# 1-POWER.net
KiCad netlist of a schematic drawn in Altium Designer
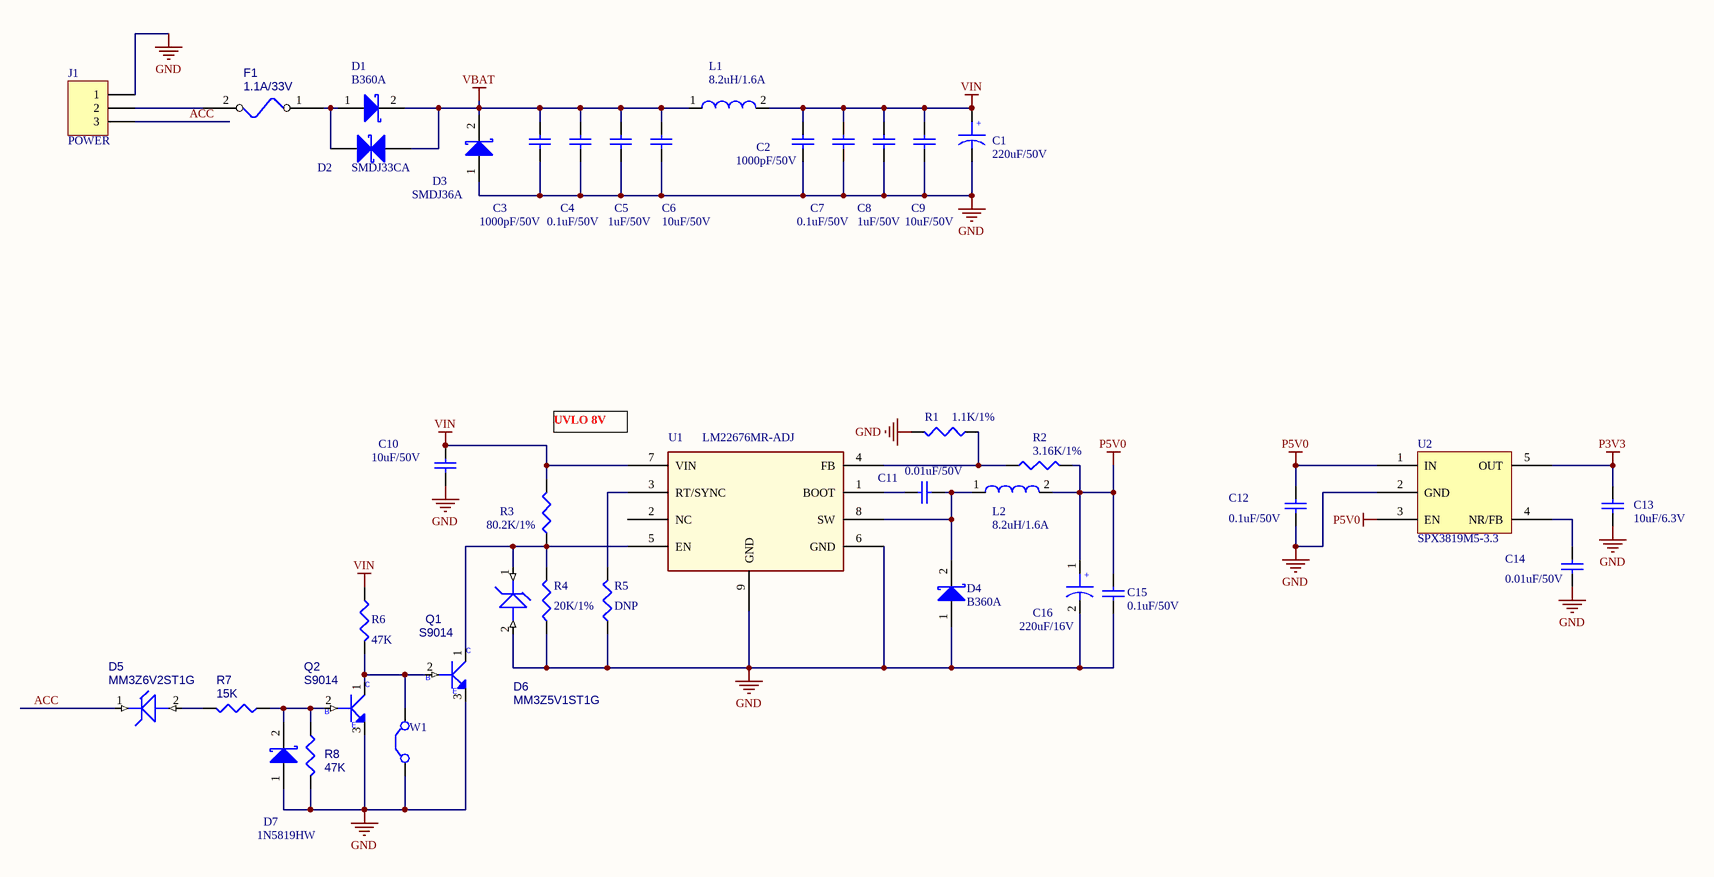
[diagram p0: 1-POWER.SchDoc]

(export (version "E")
  (design (tool "Eeschema 10.0.6"))
  (components
    (comp (ref "C1") (value "220uF/50V") (footprint "DL-10*10.5") (libsource (lib "") (part "CAP WP_1")))
    (comp (ref "C2")
      (value "1000pF/50V")
      (footprint "0402")
      (description "Capacitor")
      (fields (field (name "PUBLISHER") "Altium Limited"))
      (libsource (lib "Miscellaneous Devices") (part "Cap"))
    )
    (comp (ref "C3")
      (value "1000pF/50V")
      (footprint "0402")
      (description "Capacitor")
      (fields (field (name "PUBLISHER") "Altium Limited"))
      (libsource (lib "Miscellaneous Devices") (part "Cap"))
    )
    (comp (ref "C4")
      (value "0.1uF/50V")
      (footprint "0402")
      (description "Capacitor")
      (fields (field (name "PUBLISHER") "Altium Limited"))
      (libsource (lib "Miscellaneous Devices") (part "Cap"))
    )
    (comp (ref "C5")
      (value "1uF/50V")
      (footprint "0805")
      (description "Capacitor")
      (fields (field (name "PUBLISHER") "Altium Limited"))
      (libsource (lib "Miscellaneous Devices") (part "Cap"))
    )
    (comp (ref "C6")
      (value "10uF/50V")
      (footprint "1210")
      (description "Capacitor")
      (fields (field (name "PUBLISHER") "Altium Limited"))
      (libsource (lib "Miscellaneous Devices") (part "Cap"))
    )
    (comp (ref "C7")
      (value "0.1uF/50V")
      (footprint "0402")
      (description "Capacitor")
      (fields (field (name "PUBLISHER") "Altium Limited"))
      (libsource (lib "Miscellaneous Devices") (part "Cap"))
    )
    (comp (ref "C8")
      (value "1uF/50V")
      (footprint "0805")
      (description "Capacitor")
      (fields (field (name "PUBLISHER") "Altium Limited"))
      (libsource (lib "Miscellaneous Devices") (part "Cap"))
    )
    (comp (ref "C9")
      (value "10uF/50V")
      (footprint "1210")
      (description "Capacitor")
      (fields (field (name "PUBLISHER") "Altium Limited"))
      (libsource (lib "Miscellaneous Devices") (part "Cap"))
    )
    (comp (ref "C10")
      (value "10uF/50V")
      (footprint "1210")
      (description "Capacitor")
      (fields (field (name "PUBLISHER") "Altium Limited"))
      (libsource (lib "Miscellaneous Devices") (part "Cap"))
    )
    (comp (ref "C11")
      (value "0.01uF/50V")
      (footprint "0402")
      (description "Capacitor")
      (fields (field (name "PUBLISHER") "Altium Limited"))
      (libsource (lib "Miscellaneous Devices") (part "Cap"))
    )
    (comp (ref "C12")
      (value "0.1uF/50V")
      (footprint "0402")
      (description "Capacitor")
      (fields (field (name "PUBLISHER") "Altium Limited"))
      (libsource (lib "Miscellaneous Devices") (part "Cap"))
    )
    (comp (ref "C13")
      (value "10uF/6.3V")
      (footprint "0603")
      (description "Capacitor")
      (fields (field (name "PUBLISHER") "Altium Limited"))
      (libsource (lib "Miscellaneous Devices") (part "Cap"))
    )
    (comp (ref "C14")
      (value "0.01uF/50V")
      (footprint "0402")
      (description "Capacitor")
      (fields (field (name "PUBLISHER") "Altium Limited"))
      (libsource (lib "Miscellaneous Devices") (part "Cap"))
    )
    (comp (ref "C15")
      (value "0.1uF/50V")
      (footprint "0402")
      (description "Capacitor")
      (fields (field (name "PUBLISHER") "Altium Limited"))
      (libsource (lib "Miscellaneous Devices") (part "Cap"))
    )
    (comp (ref "C16") (value "220uF/16V") (footprint "DL-8*10.5") (libsource (lib "*") (part "CAP WP")))
    (comp (ref "D1")
      (value "B360A")
      (footprint "B320A")
      (description "Schottky Rectifier")
      (libsource (lib "Miscellaneous Devices") (part "Diode 11DQ03"))
    )
    (comp (ref "D2") (value "SMDJ33CA") (footprint "SMC") (libsource (lib "Schlib") (part "TVS-BI")))
    (comp (ref "D3")
      (value "SMDJ36A")
      (footprint "SMC")
      (description "Schottky Rectifier")
      (libsource (lib "Miscellaneous Devices") (part "Diode 11DQ03"))
    )
    (comp (ref "D4")
      (value "B360A")
      (footprint "B320A")
      (description "Schottky Rectifier")
      (libsource (lib "Miscellaneous Devices") (part "Diode 11DQ03"))
    )
    (comp (ref "D5")
      (value "MM3Z6V2ST1G")
      (footprint "SOD323F")
      (libsource (lib "*") (part "MMGZ5231BPTLL34"))
    )
    (comp (ref "D6")
      (value "MM3Z5V1ST1G")
      (footprint "SOD323F")
      (libsource (lib "*") (part "MMGZ5231BPTLL34"))
    )
    (comp (ref "D7")
      (value "1N5819HW")
      (footprint "1N5819")
      (description "Schottky Rectifier")
      (libsource (lib "Miscellaneous Devices") (part "Diode 11DQ03"))
    )
    (comp (ref "F1") (value "1.1A/33V") (footprint "1812") (libsource (lib "*") (part "2A_32VDC_0467-002")))
    (comp (ref "J1")
      (value "POWER")
      (footprint "XH2.54-SMT-V-3P")
      (description "Header, 3-Pin")
      (fields (field (name "PUBLISHER") "Altium Limited"))
      (libsource (lib "Miscellaneous Connectors") (part "Header 3"))
    )
    (comp (ref "L1")
      (value "8.2uH/1.6A")
      (footprint "IND-SMD-5.8*5.8")
      (fields (field (name "PART NUMBER") "SH00000AJ00"))
      (libsource (lib "*") (part "4.7UH_CDH2D09BNP-4R7MC_0.7A_20%"))
    )
    (comp (ref "L2")
      (value "8.2uH/1.6A")
      (footprint "IND-SMD-5.8*5.8")
      (fields (field (name "PART NUMBER") "SH00000AJ00"))
      (libsource (lib "*") (part "4.7UH_CDH2D09BNP-4R7MC_0.7A_20%"))
    )
    (comp (ref "Q1")
      (value "S9014")
      (footprint "NPN")
      (fields (field (name "PART NUMBER") "SB039040000"))
      (libsource (lib "*") (part "MMBT3904_NL_SOT23-3"))
    )
    (comp (ref "Q2")
      (value "S9014")
      (footprint "NPN")
      (fields (field (name "PART NUMBER") "SB039040000"))
      (libsource (lib "*") (part "MMBT3904_NL_SOT23-3"))
    )
    (comp (ref "R1")
      (value "1.1K/1%")
      (footprint "0402")
      (description "Resistor")
      (fields (field (name "PUBLISHER") "Altium Limited"))
      (libsource (lib "Miscellaneous Devices") (part "Res3"))
    )
    (comp (ref "R2")
      (value "3.16K/1%")
      (footprint "0402")
      (description "Resistor")
      (fields (field (name "PUBLISHER") "Altium Limited"))
      (libsource (lib "Miscellaneous Devices") (part "Res3"))
    )
    (comp (ref "R3")
      (value "80.2K/1%")
      (footprint "0402")
      (description "Resistor")
      (fields (field (name "PUBLISHER") "Altium Limited"))
      (libsource (lib "Miscellaneous Devices") (part "Res3"))
    )
    (comp (ref "R4")
      (value "20K/1%")
      (footprint "0402")
      (description "Resistor")
      (fields (field (name "PUBLISHER") "Altium Limited"))
      (libsource (lib "Miscellaneous Devices") (part "Res3"))
    )
    (comp (ref "R5")
      (value "DNP")
      (footprint "0402")
      (description "Resistor")
      (fields (field (name "PUBLISHER") "Altium Limited"))
      (libsource (lib "Miscellaneous Devices") (part "Res3"))
    )
    (comp (ref "R6")
      (value "47K")
      (footprint "0402")
      (description "Resistor")
      (fields (field (name "PUBLISHER") "Altium Limited"))
      (libsource (lib "Miscellaneous Devices") (part "Res3"))
    )
    (comp (ref "R7") (value "15K") (libsource (lib "*") (part "R")))
    (comp (ref "R8") (value "47K") (libsource (lib "*") (part "R")))
    (comp (ref "U1") (value "LM22676MR-ADJ") (libsource (lib "*") (part "LM22670_0")))
    (comp (ref "U2")
      (value "SPX3819M5-3.3")
      (footprint "SOT23-5")
      (libsource (lib "Schlib") (part "TPS73633DBVT"))
    )
    (comp (ref "W1")
      (value "Jumper")
      (footprint "SHORTCUT")
      (description "Jumper Wire")
      (fields (field (name "PUBLISHER") "Altium Limited"))
      (libsource (lib "Miscellaneous Devices") (part "Jumper"))
    )
  )
  (nets
    (net (code "1") (name "/ACC") (class "Default")
      (node (ref "D5") (pin "1") (pinfunction "1_1") (pintype "input"))
      (node (ref "J1") (pin "3") (pinfunction "3_3") (pintype "passive"))
    )
    (net (code "2") (name "GND") (class "Default")
      (node (ref "C1") (pin "2") (pinfunction "2_2") (pintype "passive"))
      (node (ref "C10") (pin "2") (pinfunction "2_2") (pintype "passive"))
      (node (ref "C12") (pin "1") (pinfunction "1_1") (pintype "passive"))
      (node (ref "C13") (pin "1") (pinfunction "1_1") (pintype "passive"))
      (node (ref "C14") (pin "1") (pinfunction "1_1") (pintype "passive"))
      (node (ref "C15") (pin "1") (pinfunction "1_1") (pintype "passive"))
      (node (ref "C16") (pin "2") (pinfunction "2_2") (pintype "passive"))
      (node (ref "C2") (pin "2") (pinfunction "2_2") (pintype "passive"))
      (node (ref "C3") (pin "2") (pinfunction "2_2") (pintype "passive"))
      (node (ref "C4") (pin "2") (pinfunction "2_2") (pintype "passive"))
      (node (ref "C5") (pin "2") (pinfunction "2_2") (pintype "passive"))
      (node (ref "C6") (pin "2") (pinfunction "2_2") (pintype "passive"))
      (node (ref "C7") (pin "2") (pinfunction "2_2") (pintype "passive"))
      (node (ref "C8") (pin "2") (pinfunction "2_2") (pintype "passive"))
      (node (ref "C9") (pin "2") (pinfunction "2_2") (pintype "passive"))
      (node (ref "D3") (pin "1") (pinfunction "A_1") (pintype "passive"))
      (node (ref "D4") (pin "1") (pinfunction "A_1") (pintype "passive"))
      (node (ref "D6") (pin "2") (pinfunction "2_2") (pintype "input"))
      (node (ref "D7") (pin "1") (pinfunction "A_1") (pintype "passive"))
      (node (ref "J1") (pin "1") (pinfunction "1_1") (pintype "passive"))
      (node (ref "Q1") (pin "3") (pinfunction "EMITTER_3") (pintype "passive"))
      (node (ref "Q2") (pin "3") (pinfunction "EMITTER_3") (pintype "passive"))
      (node (ref "R1") (pin "2") (pinfunction "2_2") (pintype "passive"))
      (node (ref "R4") (pin "1") (pinfunction "1_1") (pintype "passive"))
      (node (ref "R5") (pin "1") (pinfunction "1_1") (pintype "passive"))
      (node (ref "R8") (pin "2") (pinfunction "2_2") (pintype "passive"))
      (node (ref "U1") (pin "6") (pinfunction "GND_6") (pintype "passive"))
      (node (ref "U1") (pin "9") (pinfunction "GND_9") (pintype "power_in"))
      (node (ref "U2") (pin "2") (pinfunction "GND_2") (pintype "passive"))
      (node (ref "W1") (pin "1") (pinfunction "C1_1") (pintype "passive"))
    )
    (net (code "3") (name "Net-(D1-A)") (class "Default")
      (node (ref "D1") (pin "1") (pinfunction "A_1") (pintype "passive"))
      (node (ref "D2") (pin "1") (pinfunction "1_1") (pintype "passive"))
      (node (ref "F1") (pin "1") (pinfunction "1_1") (pintype "passive"))
    )
    (net (code "4") (name "Net-(D4-K)") (class "Default")
      (node (ref "C11") (pin "1") (pinfunction "1_1") (pintype "passive"))
      (node (ref "D4") (pin "2") (pinfunction "K_2") (pintype "passive"))
      (node (ref "L2") (pin "1") (pinfunction "1_1") (pintype "passive"))
      (node (ref "U1") (pin "8") (pinfunction "SW_8") (pintype "passive"))
    )
    (net (code "5") (name "Net-(D5-Pad2)") (class "Default")
      (node (ref "D5") (pin "2") (pinfunction "2_2") (pintype "input"))
      (node (ref "R7") (pin "2") (pinfunction "2_2") (pintype "passive"))
    )
    (net (code "6") (name "Net-(D7-K)") (class "Default")
      (node (ref "D7") (pin "2") (pinfunction "K_2") (pintype "passive"))
      (node (ref "Q2") (pin "2") (pinfunction "BASE_2") (pintype "input"))
      (node (ref "R7") (pin "1") (pinfunction "1_1") (pintype "passive"))
      (node (ref "R8") (pin "1") (pinfunction "1_1") (pintype "passive"))
    )
    (net (code "7") (name "Net-(F1-Pad2)") (class "Default")
      (node (ref "F1") (pin "2") (pinfunction "2_2") (pintype "passive"))
      (node (ref "J1") (pin "2") (pinfunction "2_2") (pintype "passive"))
    )
    (net (code "8") (name "Net-(Q1-BASE)") (class "Default")
      (node (ref "Q1") (pin "2") (pinfunction "BASE_2") (pintype "input"))
      (node (ref "Q2") (pin "1") (pinfunction "COLLECTOR_1") (pintype "passive"))
      (node (ref "R6") (pin "2") (pinfunction "2_2") (pintype "passive"))
      (node (ref "W1") (pin "2") (pinfunction "C2_2") (pintype "passive"))
    )
    (net (code "9") (name "Net-(Q1-COLLECTOR)") (class "Default")
      (node (ref "D6") (pin "1") (pinfunction "1_1") (pintype "input"))
      (node (ref "Q1") (pin "1") (pinfunction "COLLECTOR_1") (pintype "passive"))
      (node (ref "R3") (pin "1") (pinfunction "1_1") (pintype "passive"))
      (node (ref "R4") (pin "2") (pinfunction "2_2") (pintype "passive"))
      (node (ref "U1") (pin "5") (pinfunction "EN_5") (pintype "passive"))
    )
    (net (code "10") (name "Net-(U1-BOOT)") (class "Default")
      (node (ref "C11") (pin "2") (pinfunction "2_2") (pintype "passive"))
      (node (ref "U1") (pin "1") (pinfunction "BOOT_1") (pintype "passive"))
    )
    (net (code "11") (name "Net-(U1-FB)") (class "Default")
      (node (ref "R1") (pin "1") (pinfunction "1_1") (pintype "passive"))
      (node (ref "R2") (pin "1") (pinfunction "1_1") (pintype "passive"))
      (node (ref "U1") (pin "4") (pinfunction "FB_4") (pintype "passive"))
    )
    (net (code "12") (name "Net-(U1-RT{slash}SYNC)") (class "Default")
      (node (ref "R5") (pin "2") (pinfunction "2_2") (pintype "passive"))
      (node (ref "U1") (pin "3") (pinfunction "RT/SYNC_3") (pintype "passive"))
    )
    (net (code "13") (name "Net-(U2-NR{slash}FB)") (class "Default")
      (node (ref "C14") (pin "2") (pinfunction "2_2") (pintype "passive"))
      (node (ref "U2") (pin "4") (pinfunction "NR/FB_4") (pintype "passive"))
    )
    (net (code "14") (name "P3V3") (class "Default")
      (node (ref "C13") (pin "2") (pinfunction "2_2") (pintype "passive"))
      (node (ref "U2") (pin "5") (pinfunction "OUT_5") (pintype "passive"))
    )
    (net (code "15") (name "P5V0") (class "Default")
      (node (ref "C12") (pin "2") (pinfunction "2_2") (pintype "passive"))
      (node (ref "C15") (pin "2") (pinfunction "2_2") (pintype "passive"))
      (node (ref "C16") (pin "1") (pinfunction "1_1") (pintype "passive"))
      (node (ref "L2") (pin "2") (pinfunction "2_2") (pintype "passive"))
      (node (ref "R2") (pin "2") (pinfunction "2_2") (pintype "passive"))
      (node (ref "U2") (pin "1") (pinfunction "IN_1") (pintype "passive"))
      (node (ref "U2") (pin "3") (pinfunction "EN_3") (pintype "passive"))
    )
    (net (code "16") (name "VBAT") (class "Default")
      (node (ref "C3") (pin "1") (pinfunction "1_1") (pintype "passive"))
      (node (ref "C4") (pin "1") (pinfunction "1_1") (pintype "passive"))
      (node (ref "C5") (pin "1") (pinfunction "1_1") (pintype "passive"))
      (node (ref "C6") (pin "1") (pinfunction "1_1") (pintype "passive"))
      (node (ref "D1") (pin "2") (pinfunction "K_2") (pintype "passive"))
      (node (ref "D2") (pin "2") (pinfunction "2_2") (pintype "passive"))
      (node (ref "D3") (pin "2") (pinfunction "K_2") (pintype "passive"))
      (node (ref "L1") (pin "1") (pinfunction "1_1") (pintype "passive"))
    )
    (net (code "17") (name "VIN") (class "Default")
      (node (ref "C1") (pin "1") (pinfunction "1_1") (pintype "passive"))
      (node (ref "C10") (pin "1") (pinfunction "1_1") (pintype "passive"))
      (node (ref "C2") (pin "1") (pinfunction "1_1") (pintype "passive"))
      (node (ref "C7") (pin "1") (pinfunction "1_1") (pintype "passive"))
      (node (ref "C8") (pin "1") (pinfunction "1_1") (pintype "passive"))
      (node (ref "C9") (pin "1") (pinfunction "1_1") (pintype "passive"))
      (node (ref "L1") (pin "2") (pinfunction "2_2") (pintype "passive"))
      (node (ref "R3") (pin "2") (pinfunction "2_2") (pintype "passive"))
      (node (ref "R6") (pin "1") (pinfunction "1_1") (pintype "passive"))
      (node (ref "U1") (pin "7") (pinfunction "VIN_7") (pintype "power_in"))
    )
    (net (code "18") (name "unconnected-(U1-NC-Pad2)") (class "Default")
      (node (ref "U1") (pin "2") (pinfunction "NC_2") (pintype "passive"))
    )
  )
)
